# Pmod_Grove_and_Qwiic_Connections.net
KiCad netlist of a schematic drawn in Altium Designer
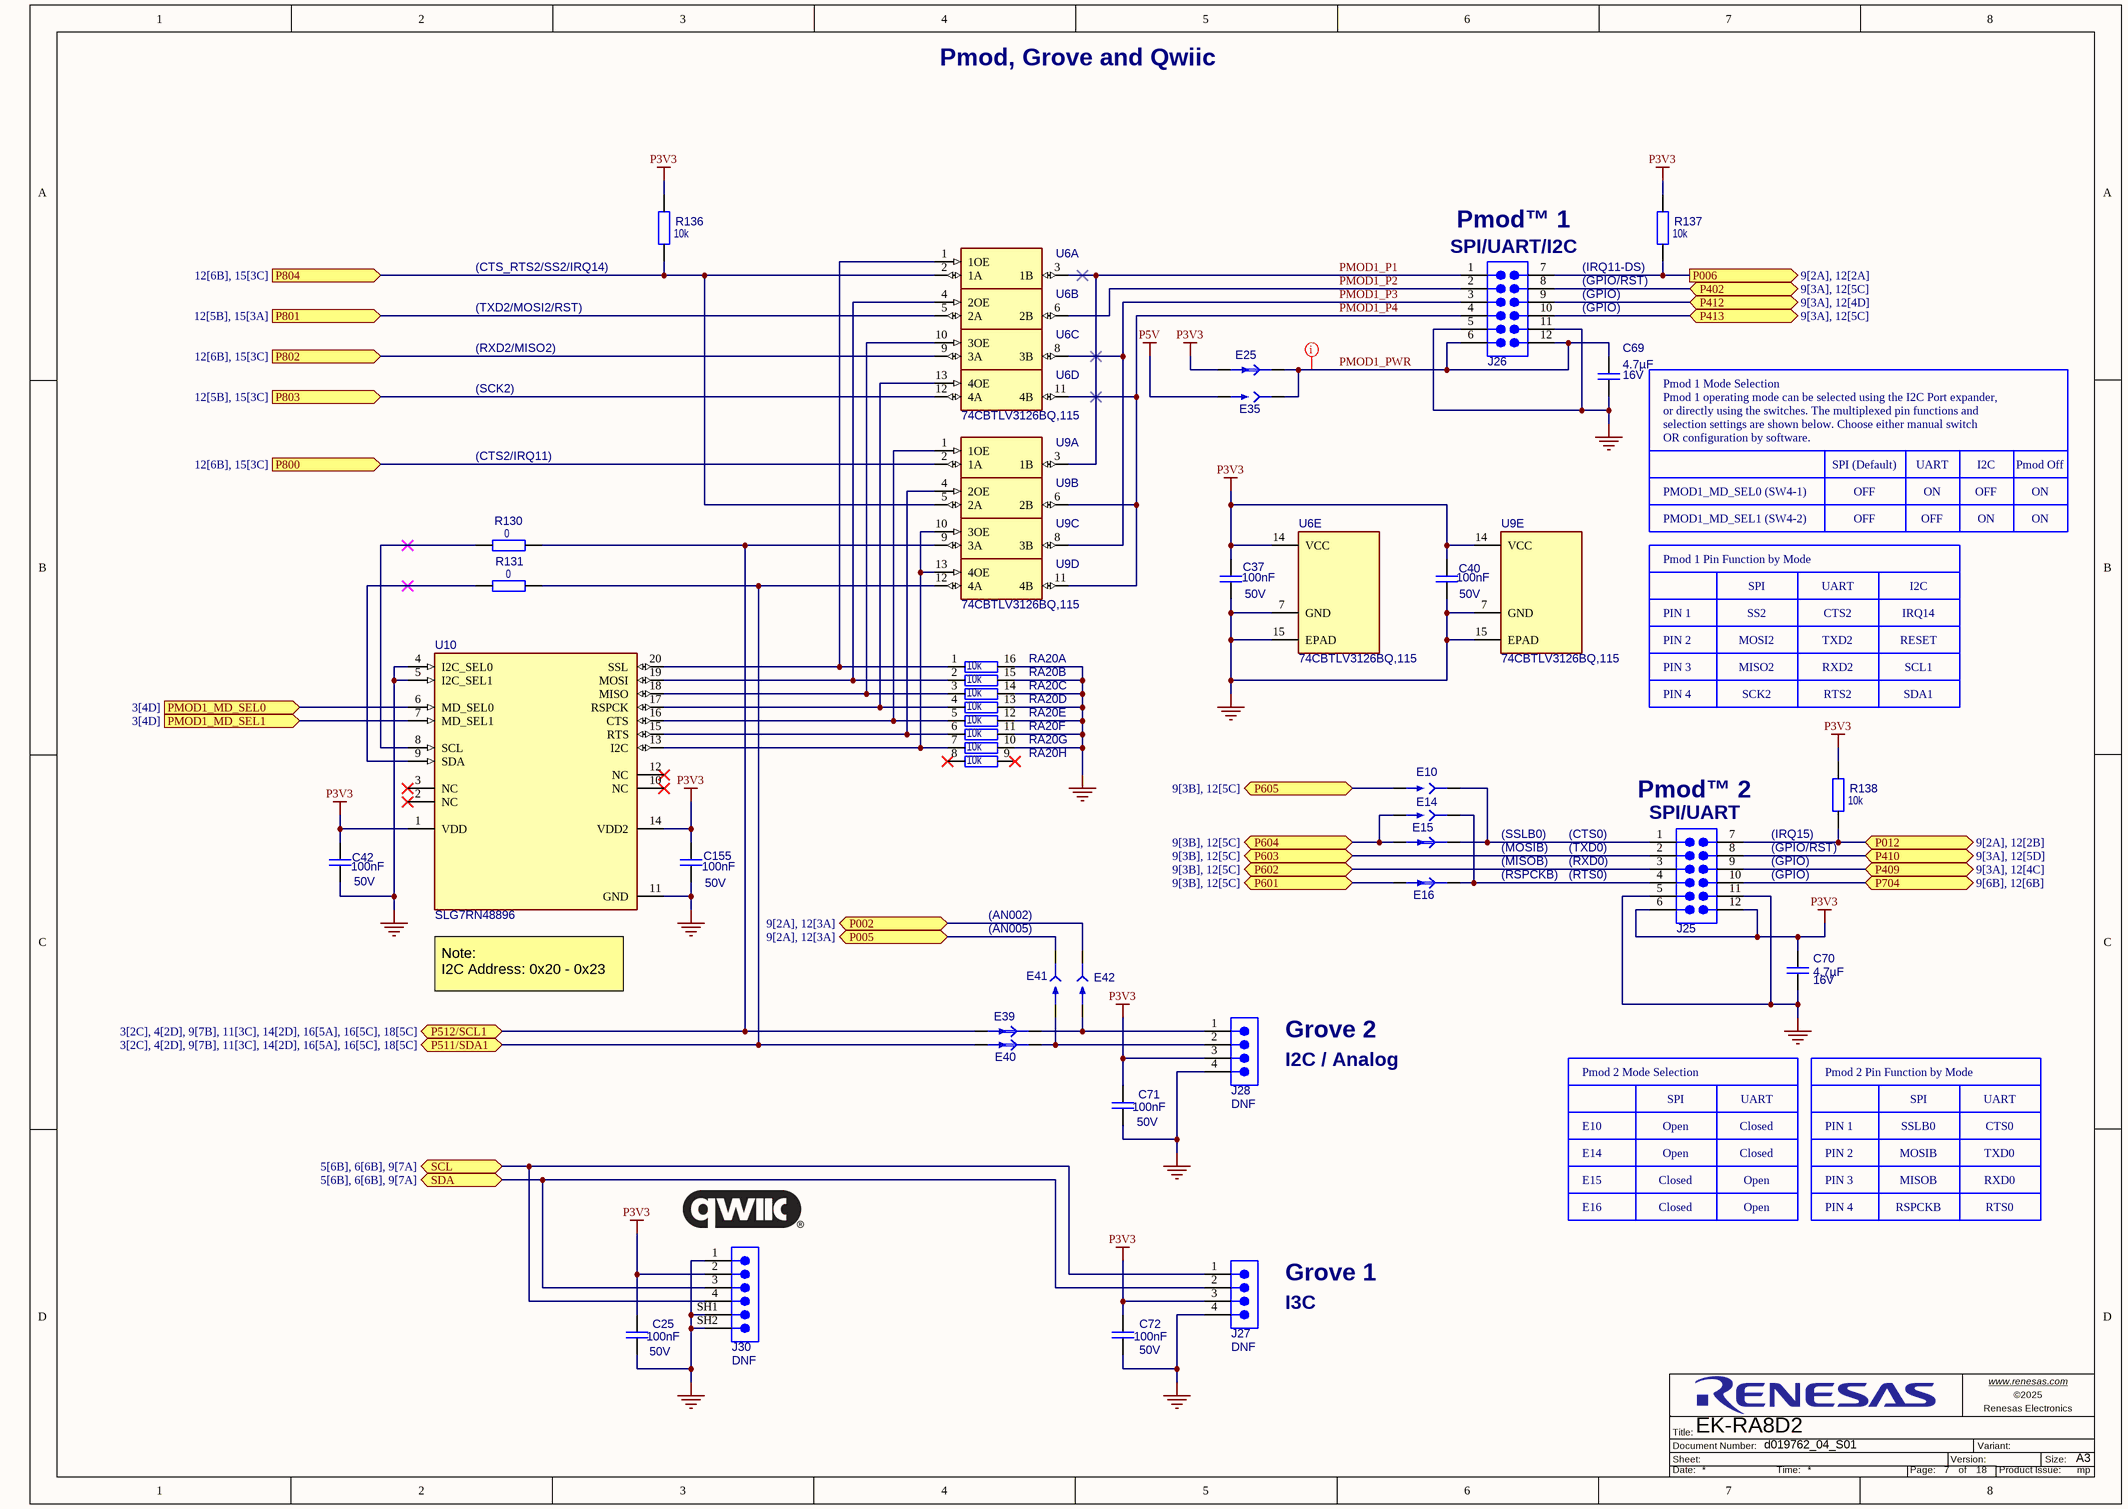
[diagram p0: Pmod, Grove and Qwiic Connections.SchDoc]

(export (version "E")
  (design (tool "Eeschema 10.0.6"))
  (components
    (comp (ref "C25")
      (value "100nF")
      (footprint "C_EIA0402_0p55")
      (description "Capacitor,EIA0402,100n,50V,X7R")
      (fields
        (field (name "TOLERANCE") "10%")
        (field (name "OPERATING VOLTAGE MAX") "50V")
        (field (name "Comment") "Capacitor")
      )
      (libsource (lib "ek-ra8d2_mp - Customer") (part "Capacitor"))
    )
    (comp (ref "C37")
      (value "100nF")
      (footprint "C_EIA0402_0p55")
      (description "Capacitor,EIA0402,100n,50V,X7R")
      (fields
        (field (name "TOLERANCE") "10%")
        (field (name "OPERATING VOLTAGE MAX") "50V")
        (field (name "Comment") "Capacitor")
      )
      (libsource (lib "ek-ra8d2_mp - Customer") (part "Capacitor"))
    )
    (comp (ref "C40")
      (value "100nF")
      (footprint "C_EIA0402_0p55")
      (description "Capacitor,EIA0402,100n,50V,X7R")
      (fields
        (field (name "TOLERANCE") "10%")
        (field (name "OPERATING VOLTAGE MAX") "50V")
        (field (name "Comment") "Capacitor")
      )
      (libsource (lib "ek-ra8d2_mp - Customer") (part "Capacitor"))
    )
    (comp (ref "C42")
      (value "100nF")
      (footprint "C_EIA0402_0p55")
      (description "Capacitor,EIA0402,100n,50V,X7R")
      (fields
        (field (name "TOLERANCE") "10%")
        (field (name "OPERATING VOLTAGE MAX") "50V")
        (field (name "Comment") "Capacitor")
      )
      (libsource (lib "ek-ra8d2_mp - Customer") (part "Capacitor"))
    )
    (comp (ref "C69")
      (value "4.7µF")
      (footprint "C_EIA0603_1p0")
      (description "Capacitor,EIA0603,4.7u,16V,X7S")
      (fields
        (field (name "TOLERANCE") "10%")
        (field (name "OPERATING VOLTAGE MAX") "16V")
        (field (name "Comment") "Capacitor")
      )
      (libsource (lib "ek-ra8d2_mp - Customer") (part "Capacitor"))
    )
    (comp (ref "C70")
      (value "4.7µF")
      (footprint "C_EIA0603_1p0")
      (description "Capacitor,EIA0603,4.7u,16V,X7S")
      (fields
        (field (name "TOLERANCE") "10%")
        (field (name "OPERATING VOLTAGE MAX") "16V")
        (field (name "Comment") "Capacitor")
      )
      (libsource (lib "ek-ra8d2_mp - Customer") (part "Capacitor"))
    )
    (comp (ref "C71")
      (value "100nF")
      (footprint "C_EIA0402_0p55")
      (description "Capacitor,EIA0402,100n,50V,X7R")
      (fields
        (field (name "TOLERANCE") "10%")
        (field (name "OPERATING VOLTAGE MAX") "50V")
        (field (name "Comment") "Capacitor")
      )
      (libsource (lib "ek-ra8d2_mp - Customer") (part "Capacitor"))
    )
    (comp (ref "C72")
      (value "100nF")
      (footprint "C_EIA0402_0p55")
      (description "Capacitor,EIA0402,100n,50V,X7R")
      (fields
        (field (name "TOLERANCE") "10%")
        (field (name "OPERATING VOLTAGE MAX") "50V")
        (field (name "Comment") "Capacitor")
      )
      (libsource (lib "ek-ra8d2_mp - Customer") (part "Capacitor"))
    )
    (comp (ref "C155")
      (value "100nF")
      (footprint "C_EIA0402_0p55")
      (description "Capacitor,EIA0402,100n,50V,X7R")
      (fields
        (field (name "TOLERANCE") "10%")
        (field (name "OPERATING VOLTAGE MAX") "50V")
        (field (name "Comment") "Capacitor")
      )
      (libsource (lib "ek-ra8d2_mp - Customer") (part "Capacitor"))
    )
    (comp (ref "E10")
      (value "SOLDER_BRIDGE_0805")
      (footprint "solder_bridge_0805")
      (description "Solder Bridge, SMD, 0805 size")
      (libsource (lib "ek-ra8d2_mp - Customer") (part "solder_bridge"))
    )
    (comp (ref "E14")
      (value "SOLDER_BRIDGE_0805")
      (footprint "solder_bridge_0805")
      (description "Solder Bridge, SMD, 0805 size")
      (libsource (lib "ek-ra8d2_mp - Customer") (part "solder_bridge"))
    )
    (comp (ref "E15")
      (value "TRACE_CUT_0805")
      (footprint "trace_cut_0805")
      (description "Trace Cut, SMD, 0805 size")
      (libsource (lib "ek-ra8d2_mp - Customer") (part "trace_cut"))
    )
    (comp (ref "E16")
      (value "TRACE_CUT_0805")
      (footprint "trace_cut_0805")
      (description "Trace Cut, SMD, 0805 size")
      (libsource (lib "ek-ra8d2_mp - Customer") (part "trace_cut"))
    )
    (comp (ref "E25")
      (value "TRACE_CUT_0805")
      (footprint "trace_cut_0805")
      (description "Trace Cut, SMD, 0805 size")
      (libsource (lib "ek-ra8d2_mp - Customer") (part "trace_cut"))
    )
    (comp (ref "E35")
      (value "SOLDER_BRIDGE_0805")
      (footprint "solder_bridge_0805")
      (description "Solder Bridge, SMD, 0805 size")
      (libsource (lib "ek-ra8d2_mp - Customer") (part "solder_bridge"))
    )
    (comp (ref "E39")
      (value "TRACE_CUT_0805")
      (footprint "trace_cut_0805")
      (description "Trace Cut, SMD, 0805 size")
      (libsource (lib "ek-ra8d2_mp - Customer") (part "trace_cut"))
    )
    (comp (ref "E40")
      (value "TRACE_CUT_0805")
      (footprint "trace_cut_0805")
      (description "Trace Cut, SMD, 0805 size")
      (libsource (lib "ek-ra8d2_mp - Customer") (part "trace_cut"))
    )
    (comp (ref "E41")
      (value "SOLDER_BRIDGE_0805")
      (footprint "solder_bridge_0805")
      (description "Solder Bridge, SMD, 0805 size")
      (libsource (lib "ek-ra8d2_mp - Customer") (part "solder_bridge"))
    )
    (comp (ref "E42")
      (value "SOLDER_BRIDGE_0805")
      (footprint "solder_bridge_0805")
      (description "Solder Bridge, SMD, 0805 size")
      (libsource (lib "ek-ra8d2_mp - Customer") (part "solder_bridge"))
    )
    (comp (ref "J25")
      (value "SMH-106-02-L-D")
      (footprint "sam_SMH-106-02-LD_PMOD")
      (description "Socket,12way,2row,horizontal,2.54mm,SMD,PMOD_Interface")
      (libsource (lib "ek-ra8d2_mp - Customer") (part "CON_012"))
    )
    (comp (ref "J26")
      (value "SMH-106-02-L-D")
      (footprint "sam_SMH-106-02-LD_PMOD")
      (description "Socket,12way,2row,horizontal,2.54mm,SMD,PMOD_Interface")
      (libsource (lib "ek-ra8d2_mp - Customer") (part "CON_012"))
    )
    (comp (ref "J27")
      (value "110990037")
      (footprint "sed_110990037")
      (description "Grove Header,4Way,1 Row, Horizontal,2mm,THT")
      (fields (field (name "DNF") "DNF"))
      (libsource (lib "ek-ra8d2_mp - Customer") (part "CON_004"))
    )
    (comp (ref "J28")
      (value "110990037")
      (footprint "sed_110990037")
      (description "Grove Header,4Way,1 Row, Horizontal,2mm,THT")
      (fields (field (name "DNF") "DNF"))
      (libsource (lib "ek-ra8d2_mp - Customer") (part "CON_004"))
    )
    (comp (ref "J30")
      (value "SM04B-SRSS-TB(LF)(SN)")
      (footprint "jst_SM04B-SRSS-TB(LF)(SN)")
      (description "Wire-to-Board Header,4way, Single Row, Right-Angle, SMD")
      (fields (field (name "DNF") "DNF"))
      (libsource (lib "ek-ra8d2_mp - Customer") (part "CON_004_MNT2"))
    )
    (comp (ref "R130")
      (value "0")
      (footprint "R_EIA0402")
      (description "Resistor,EIA0402,0,0.0625W")
      (fields (field (name "POWER") "62.5mW") (field (name "TOLERANCE") "5%"))
      (libsource (lib "ek-ra8d2_mp - Customer") (part "Resistor"))
    )
    (comp (ref "R131")
      (value "0")
      (footprint "R_EIA0402")
      (description "Resistor,EIA0402,0,0.0625W")
      (fields (field (name "POWER") "62.5mW") (field (name "TOLERANCE") "5%"))
      (libsource (lib "ek-ra8d2_mp - Customer") (part "Resistor"))
    )
    (comp (ref "R136")
      (value "10k")
      (footprint "R_EIA0402")
      (description "Resistor,EIA0402,10k,0.0625W")
      (fields (field (name "POWER") "62.5mW") (field (name "TOLERANCE") "1%"))
      (libsource (lib "") (part "Resistor_1"))
    )
    (comp (ref "R137")
      (value "10k")
      (footprint "R_EIA0402")
      (description "Resistor,EIA0402,10k,0.0625W")
      (fields (field (name "POWER") "62.5mW") (field (name "TOLERANCE") "1%"))
      (libsource (lib "") (part "Resistor_1"))
    )
    (comp (ref "R138")
      (value "10k")
      (footprint "R_EIA0402")
      (description "Resistor,EIA0402,10k,0.0625W")
      (fields (field (name "POWER") "62.5mW") (field (name "TOLERANCE") "1%"))
      (libsource (lib "") (part "Resistor_1"))
    )
    (comp (ref "RA20")
      (value "10k")
      (footprint "R_Array_EIA1506")
      (description "Resistor Network & Array,EIA1506,10k,0.063W")
      (fields (field (name "TOLERANCE") "5%") (field (name "POWER") "62.5mW"))
      (libsource (lib "ek-ra8d2_mp - Customer") (part "Resistor_Array_16-Leads"))
    )
    (comp (ref "U6")
      (value "74CBTLV3126BQ,115")
      (footprint "nex_DHVQFN14_SOT-762-1_MO-241")
      (description "Bus Driver, 4-Func, 1-Bit, True Output, CMOS, DHVQN14, SOT762-1")
      (fields (field (name "POWER") "500mW"))
      (libsource (lib "ek-ra8d2_mp - Customer") (part "nex_74CBTLV3126"))
    )
    (comp (ref "U9")
      (value "74CBTLV3126BQ,115")
      (footprint "nex_DHVQFN14_SOT-762-1_MO-241")
      (description "Bus Driver, 4-Func, 1-Bit, True Output, CMOS, DHVQN14, SOT762-1")
      (fields (field (name "POWER") "500mW"))
      (libsource (lib "ek-ra8d2_mp - Customer") (part "nex_74CBTLV3126"))
    )
    (comp (ref "U10")
      (value "SLG7RN48896")
      (footprint "ren_STQFN-20_2x3")
      (description "Renesas GreenPak PMOD mode controller")
      (libsource (lib "ek-ra8d2_mp - Customer") (part "ren_SLG7RN48896"))
    )
  )
  (nets
    (net (code "1") (name "/P002") (class "Default")
      (node (ref "E42") (pin "1") (pinfunction "1_1") (pintype "passive"))
    )
    (net (code "2") (name "/P005") (class "Default")
      (node (ref "E41") (pin "1") (pinfunction "1_1") (pintype "passive"))
    )
    (net (code "3") (name "/P006") (class "Default")
      (node (ref "J26") (pin "7") (pinfunction "7_7") (pintype "passive"))
      (node (ref "R137") (pin "1") (pinfunction "1_1") (pintype "passive"))
    )
    (net (code "4") (name "/P012") (class "Default")
      (node (ref "J25") (pin "7") (pinfunction "7_7") (pintype "passive"))
      (node (ref "R138") (pin "1") (pinfunction "1_1") (pintype "passive"))
    )
    (net (code "5") (name "/P402") (class "Default")
      (node (ref "J26") (pin "8") (pinfunction "8_8") (pintype "passive"))
    )
    (net (code "6") (name "/P409") (class "Default")
      (node (ref "J25") (pin "9") (pinfunction "9_9") (pintype "passive"))
    )
    (net (code "7") (name "/P410") (class "Default")
      (node (ref "J25") (pin "8") (pinfunction "8_8") (pintype "passive"))
    )
    (net (code "8") (name "/P412") (class "Default")
      (node (ref "J26") (pin "9") (pinfunction "9_9") (pintype "passive"))
    )
    (net (code "9") (name "/P413") (class "Default")
      (node (ref "J26") (pin "10") (pinfunction "10_10") (pintype "passive"))
    )
    (net (code "10") (name "/P511{slash}SDA1") (class "Default")
      (node (ref "E40") (pin "2") (pinfunction "2_2") (pintype "passive"))
      (node (ref "R131") (pin "1") (pinfunction "1_1") (pintype "passive"))
      (node (ref "U9") (pin "12") (pinfunction "4A_12") (pintype "bidirectional"))
    )
    (net (code "11") (name "/P512{slash}SCL1") (class "Default")
      (node (ref "E39") (pin "2") (pinfunction "2_2") (pintype "passive"))
      (node (ref "R130") (pin "1") (pinfunction "1_1") (pintype "passive"))
      (node (ref "U9") (pin "9") (pinfunction "3A_9") (pintype "bidirectional"))
    )
    (net (code "12") (name "/P601") (class "Default")
      (node (ref "E16") (pin "2") (pinfunction "2_2") (pintype "passive"))
    )
    (net (code "13") (name "/P602") (class "Default")
      (node (ref "J25") (pin "3") (pinfunction "3_3") (pintype "passive"))
    )
    (net (code "14") (name "/P603") (class "Default")
      (node (ref "J25") (pin "2") (pinfunction "2_2") (pintype "passive"))
    )
    (net (code "15") (name "/P604") (class "Default")
      (node (ref "E14") (pin "2") (pinfunction "2_2") (pintype "passive"))
      (node (ref "E15") (pin "2") (pinfunction "2_2") (pintype "passive"))
    )
    (net (code "16") (name "/P605") (class "Default")
      (node (ref "E10") (pin "2") (pinfunction "2_2") (pintype "passive"))
    )
    (net (code "17") (name "/P704") (class "Default")
      (node (ref "J25") (pin "10") (pinfunction "10_10") (pintype "passive"))
    )
    (net (code "18") (name "/P800") (class "Default")
      (node (ref "U9") (pin "2") (pinfunction "1A_2") (pintype "bidirectional"))
    )
    (net (code "19") (name "/P801") (class "Default")
      (node (ref "U6") (pin "5") (pinfunction "2A_5") (pintype "bidirectional"))
    )
    (net (code "20") (name "/P802") (class "Default")
      (node (ref "U6") (pin "9") (pinfunction "3A_9") (pintype "bidirectional"))
    )
    (net (code "21") (name "/P803") (class "Default")
      (node (ref "U6") (pin "12") (pinfunction "4A_12") (pintype "bidirectional"))
    )
    (net (code "22") (name "/P804") (class "Default")
      (node (ref "R136") (pin "1") (pinfunction "1_1") (pintype "passive"))
      (node (ref "U6") (pin "2") (pinfunction "1A_2") (pintype "bidirectional"))
      (node (ref "U9") (pin "5") (pinfunction "2A_5") (pintype "bidirectional"))
    )
    (net (code "23") (name "/PMOD1_MD_SEL0") (class "Default")
      (node (ref "U10") (pin "6") (pinfunction "MD_SEL0_6") (pintype "input"))
    )
    (net (code "24") (name "/PMOD1_MD_SEL1") (class "Default")
      (node (ref "U10") (pin "7") (pinfunction "MD_SEL1_7") (pintype "input"))
    )
    (net (code "25") (name "/PMOD1_P1") (class "Default")
      (node (ref "J26") (pin "1") (pinfunction "1_1") (pintype "passive"))
      (node (ref "U6") (pin "3") (pinfunction "1B_3") (pintype "bidirectional"))
      (node (ref "U9") (pin "3") (pinfunction "1B_3") (pintype "bidirectional"))
    )
    (net (code "26") (name "/PMOD1_P2") (class "Default")
      (node (ref "J26") (pin "2") (pinfunction "2_2") (pintype "passive"))
      (node (ref "U6") (pin "6") (pinfunction "2B_6") (pintype "bidirectional"))
    )
    (net (code "27") (name "/PMOD1_P3") (class "Default")
      (node (ref "J26") (pin "3") (pinfunction "3_3") (pintype "passive"))
      (node (ref "U6") (pin "8") (pinfunction "3B_8") (pintype "bidirectional"))
      (node (ref "U9") (pin "8") (pinfunction "3B_8") (pintype "bidirectional"))
    )
    (net (code "28") (name "/PMOD1_P4") (class "Default")
      (node (ref "J26") (pin "4") (pinfunction "4_4") (pintype "passive"))
      (node (ref "U6") (pin "11") (pinfunction "4B_11") (pintype "bidirectional"))
      (node (ref "U9") (pin "11") (pinfunction "4B_11") (pintype "bidirectional"))
      (node (ref "U9") (pin "6") (pinfunction "2B_6") (pintype "bidirectional"))
    )
    (net (code "29") (name "/PMOD1_PWR") (class "Default")
      (node (ref "C69") (pin "1") (pinfunction "1_1") (pintype "passive"))
      (node (ref "E25") (pin "1") (pinfunction "1_1") (pintype "passive"))
      (node (ref "E35") (pin "1") (pinfunction "1_1") (pintype "passive"))
      (node (ref "J26") (pin "12") (pinfunction "12_12") (pintype "passive"))
      (node (ref "J26") (pin "6") (pinfunction "6_6") (pintype "passive"))
    )
    (net (code "30") (name "/SCL") (class "Default")
      (node (ref "J27") (pin "1") (pinfunction "1_1") (pintype "passive"))
      (node (ref "J30") (pin "4") (pinfunction "4_4") (pintype "passive"))
    )
    (net (code "31") (name "/SDA") (class "Default")
      (node (ref "J27") (pin "2") (pinfunction "2_2") (pintype "passive"))
      (node (ref "J30") (pin "3") (pinfunction "3_3") (pintype "passive"))
    )
    (net (code "32") (name "GND") (class "Default")
      (node (ref "C155") (pin "1") (pinfunction "1_1") (pintype "passive"))
      (node (ref "C25") (pin "1") (pinfunction "1_1") (pintype "passive"))
      (node (ref "C37") (pin "1") (pinfunction "1_1") (pintype "passive"))
      (node (ref "C40") (pin "1") (pinfunction "1_1") (pintype "passive"))
      (node (ref "C42") (pin "1") (pinfunction "1_1") (pintype "passive"))
      (node (ref "C69") (pin "2") (pinfunction "2_2") (pintype "passive"))
      (node (ref "C70") (pin "2") (pinfunction "2_2") (pintype "passive"))
      (node (ref "C71") (pin "1") (pinfunction "1_1") (pintype "passive"))
      (node (ref "C72") (pin "1") (pinfunction "1_1") (pintype "passive"))
      (node (ref "J25") (pin "11") (pinfunction "11_11") (pintype "passive"))
      (node (ref "J25") (pin "5") (pinfunction "5_5") (pintype "passive"))
      (node (ref "J26") (pin "11") (pinfunction "11_11") (pintype "passive"))
      (node (ref "J26") (pin "5") (pinfunction "5_5") (pintype "passive"))
      (node (ref "J27") (pin "4") (pinfunction "4_4") (pintype "passive"))
      (node (ref "J28") (pin "4") (pinfunction "4_4") (pintype "passive"))
      (node (ref "J30") (pin "1") (pinfunction "1_1") (pintype "passive"))
      (node (ref "J30") (pin "SH1") (pinfunction "SH2_SH1") (pintype "passive"))
      (node (ref "J30") (pin "SH2") (pinfunction "SH2_SH2") (pintype "passive"))
      (node (ref "RA20") (pin "10") (pinfunction "10_10") (pintype "passive"))
      (node (ref "RA20") (pin "11") (pinfunction "11_11") (pintype "passive"))
      (node (ref "RA20") (pin "12") (pinfunction "12_12") (pintype "passive"))
      (node (ref "RA20") (pin "13") (pinfunction "13_13") (pintype "passive"))
      (node (ref "RA20") (pin "14") (pinfunction "14_14") (pintype "passive"))
      (node (ref "RA20") (pin "15") (pinfunction "15_15") (pintype "passive"))
      (node (ref "RA20") (pin "16") (pinfunction "16_16") (pintype "passive"))
      (node (ref "U10") (pin "11") (pinfunction "GND_11") (pintype "power_in"))
      (node (ref "U10") (pin "4") (pinfunction "I2C_SEL0_4") (pintype "input"))
      (node (ref "U10") (pin "5") (pinfunction "I2C_SEL1_5") (pintype "input"))
      (node (ref "U6") (pin "15") (pinfunction "EPAD_15") (pintype "power_in"))
      (node (ref "U6") (pin "7") (pinfunction "GND_7") (pintype "power_in"))
      (node (ref "U9") (pin "15") (pinfunction "EPAD_15") (pintype "power_in"))
      (node (ref "U9") (pin "7") (pinfunction "GND_7") (pintype "power_in"))
    )
    (net (code "33") (name "Net-(E10-Pad1)") (class "Default")
      (node (ref "E10") (pin "1") (pinfunction "1_1") (pintype "passive"))
      (node (ref "E15") (pin "1") (pinfunction "1_1") (pintype "passive"))
      (node (ref "J25") (pin "1") (pinfunction "1_1") (pintype "passive"))
    )
    (net (code "34") (name "Net-(E14-Pad1)") (class "Default")
      (node (ref "E14") (pin "1") (pinfunction "1_1") (pintype "passive"))
      (node (ref "E16") (pin "1") (pinfunction "1_1") (pintype "passive"))
      (node (ref "J25") (pin "4") (pinfunction "4_4") (pintype "passive"))
    )
    (net (code "35") (name "Net-(E39-Pad1)") (class "Default")
      (node (ref "E39") (pin "1") (pinfunction "1_1") (pintype "passive"))
      (node (ref "E42") (pin "2") (pinfunction "2_2") (pintype "passive"))
      (node (ref "J28") (pin "1") (pinfunction "1_1") (pintype "passive"))
    )
    (net (code "36") (name "Net-(E40-Pad1)") (class "Default")
      (node (ref "E40") (pin "1") (pinfunction "1_1") (pintype "passive"))
      (node (ref "E41") (pin "2") (pinfunction "2_2") (pintype "passive"))
      (node (ref "J28") (pin "2") (pinfunction "2_2") (pintype "passive"))
    )
    (net (code "37") (name "Net-(U10-CTS)") (class "Default")
      (node (ref "RA20") (pin "5") (pinfunction "5_5") (pintype "passive"))
      (node (ref "U10") (pin "16") (pinfunction "CTS_16") (pintype "bidirectional"))
      (node (ref "U9") (pin "1") (pinfunction "1OE_1") (pintype "input"))
    )
    (net (code "38") (name "Net-(U10-I2C)") (class "Default")
      (node (ref "RA20") (pin "7") (pinfunction "7_7") (pintype "passive"))
      (node (ref "U10") (pin "13") (pinfunction "I2C_13") (pintype "bidirectional"))
      (node (ref "U9") (pin "10") (pinfunction "3OE_10") (pintype "input"))
      (node (ref "U9") (pin "13") (pinfunction "4OE_13") (pintype "input"))
    )
    (net (code "39") (name "Net-(U10-MISO)") (class "Default")
      (node (ref "RA20") (pin "3") (pinfunction "3_3") (pintype "passive"))
      (node (ref "U10") (pin "18") (pinfunction "MISO_18") (pintype "bidirectional"))
      (node (ref "U6") (pin "10") (pinfunction "3OE_10") (pintype "input"))
    )
    (net (code "40") (name "Net-(U10-MOSI)") (class "Default")
      (node (ref "RA20") (pin "2") (pinfunction "2_2") (pintype "passive"))
      (node (ref "U10") (pin "19") (pinfunction "MOSI_19") (pintype "bidirectional"))
      (node (ref "U6") (pin "4") (pinfunction "2OE_4") (pintype "input"))
    )
    (net (code "41") (name "Net-(U10-RSPCK)") (class "Default")
      (node (ref "RA20") (pin "4") (pinfunction "4_4") (pintype "passive"))
      (node (ref "U10") (pin "17") (pinfunction "RSPCK_17") (pintype "bidirectional"))
      (node (ref "U6") (pin "13") (pinfunction "4OE_13") (pintype "input"))
    )
    (net (code "42") (name "Net-(U10-RTS)") (class "Default")
      (node (ref "RA20") (pin "6") (pinfunction "6_6") (pintype "passive"))
      (node (ref "U10") (pin "15") (pinfunction "RTS_15") (pintype "bidirectional"))
      (node (ref "U9") (pin "4") (pinfunction "2OE_4") (pintype "input"))
    )
    (net (code "43") (name "Net-(U10-SCL)") (class "Default")
      (node (ref "R130") (pin "2") (pinfunction "2_2") (pintype "passive"))
      (node (ref "U10") (pin "8") (pinfunction "SCL_8") (pintype "input"))
    )
    (net (code "44") (name "Net-(U10-SDA)") (class "Default")
      (node (ref "R131") (pin "2") (pinfunction "2_2") (pintype "passive"))
      (node (ref "U10") (pin "9") (pinfunction "SDA_9") (pintype "input"))
    )
    (net (code "45") (name "Net-(U10-SSL)") (class "Default")
      (node (ref "RA20") (pin "1") (pinfunction "1_1") (pintype "passive"))
      (node (ref "U10") (pin "20") (pinfunction "SSL_20") (pintype "bidirectional"))
      (node (ref "U6") (pin "1") (pinfunction "1OE_1") (pintype "input"))
    )
    (net (code "46") (name "P3V3") (class "Default")
      (node (ref "C155") (pin "2") (pinfunction "2_2") (pintype "passive"))
      (node (ref "C25") (pin "2") (pinfunction "2_2") (pintype "passive"))
      (node (ref "C37") (pin "2") (pinfunction "2_2") (pintype "passive"))
      (node (ref "C40") (pin "2") (pinfunction "2_2") (pintype "passive"))
      (node (ref "C42") (pin "2") (pinfunction "2_2") (pintype "passive"))
      (node (ref "C70") (pin "1") (pinfunction "1_1") (pintype "passive"))
      (node (ref "C71") (pin "2") (pinfunction "2_2") (pintype "passive"))
      (node (ref "C72") (pin "2") (pinfunction "2_2") (pintype "passive"))
      (node (ref "E25") (pin "2") (pinfunction "2_2") (pintype "passive"))
      (node (ref "J25") (pin "12") (pinfunction "12_12") (pintype "passive"))
      (node (ref "J25") (pin "6") (pinfunction "6_6") (pintype "passive"))
      (node (ref "J27") (pin "3") (pinfunction "3_3") (pintype "passive"))
      (node (ref "J28") (pin "3") (pinfunction "3_3") (pintype "passive"))
      (node (ref "J30") (pin "2") (pinfunction "2_2") (pintype "passive"))
      (node (ref "R136") (pin "2") (pinfunction "2_2") (pintype "passive"))
      (node (ref "R137") (pin "2") (pinfunction "2_2") (pintype "passive"))
      (node (ref "R138") (pin "2") (pinfunction "2_2") (pintype "passive"))
      (node (ref "U10") (pin "1") (pinfunction "VDD_1") (pintype "power_in"))
      (node (ref "U10") (pin "14") (pinfunction "VDD2_14") (pintype "power_in"))
      (node (ref "U6") (pin "14") (pinfunction "VCC_14") (pintype "power_in"))
      (node (ref "U9") (pin "14") (pinfunction "VCC_14") (pintype "power_in"))
    )
    (net (code "47") (name "P5V") (class "Default")
      (node (ref "E35") (pin "2") (pinfunction "2_2") (pintype "passive"))
    )
    (net (code "48") (name "unconnected-(RA20-Pad8)") (class "Default")
      (node (ref "RA20") (pin "8") (pinfunction "8_8") (pintype "passive+no_connect"))
    )
    (net (code "49") (name "unconnected-(RA20-Pad9)") (class "Default")
      (node (ref "RA20") (pin "9") (pinfunction "9_9") (pintype "passive+no_connect"))
    )
    (net (code "50") (name "unconnected-(U10-NC-Pad2)") (class "Default")
      (node (ref "U10") (pin "2") (pinfunction "NC_2") (pintype "passive+no_connect"))
    )
    (net (code "51") (name "unconnected-(U10-NC-Pad3)") (class "Default")
      (node (ref "U10") (pin "3") (pinfunction "NC_3") (pintype "passive+no_connect"))
    )
    (net (code "52") (name "unconnected-(U10-NC-Pad10)") (class "Default")
      (node (ref "U10") (pin "10") (pinfunction "NC_10") (pintype "passive+no_connect"))
    )
    (net (code "53") (name "unconnected-(U10-NC-Pad12)") (class "Default")
      (node (ref "U10") (pin "12") (pinfunction "NC_12") (pintype "passive+no_connect"))
    )
  )
)
